# EMF_Trinket.net
KiCad netlist of a schematic drawn in EAGLE
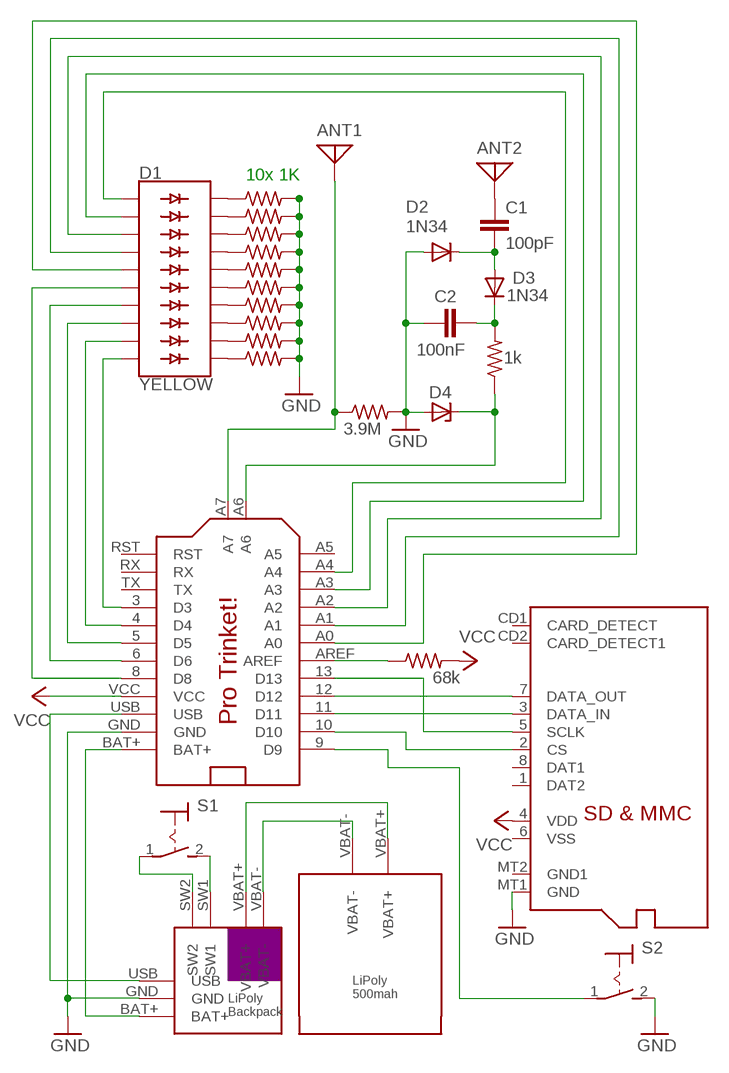
[diagram p0: schematic, sheet 1]

(export (version "E")
  (design (tool "Eeschema 10.0.6"))
  (components
    (comp (ref "ANT1")
      (value "ANTENNA")
      (footprint "eagle-import:PAD-01")
      (libsource (lib "eagle-import") (part "ANTENNA"))
    )
    (comp (ref "ANT2")
      (value "ANTENNA")
      (footprint "eagle-import:PAD-01")
      (libsource (lib "eagle-import") (part "ANTENNA"))
    )
    (comp (ref "C1")
      (value "100pF")
      (footprint "eagle-import:C5B2.5")
      (libsource (lib "eagle-import") (part "C5/2.5"))
    )
    (comp (ref "C2")
      (value "100nF")
      (footprint "eagle-import:C5B2.5")
      (libsource (lib "eagle-import") (part "C5/2.5"))
    )
    (comp (ref "D1")
      (value "YELLOW")
      (footprint "eagle-import:LED_BARGRAPH_10")
      (libsource (lib "eagle-import") (part "LED_BARGRAPH_10YELLOW"))
    )
    (comp (ref "D2")
      (value "1N34")
      (footprint "eagle-import:DO07")
      (libsource (lib "eagle-import") (part "AA112"))
    )
    (comp (ref "D3")
      (value "1N34")
      (footprint "eagle-import:DO07")
      (libsource (lib "eagle-import") (part "AA112"))
    )
    (comp (ref "D4")
      (value "ZENER-DIODEDO35Z10")
      (footprint "eagle-import:DO35Z10")
      (libsource (lib "eagle-import") (part "ZENER-DIODEDO35Z10"))
    )
    (comp (ref "R1")
      (value "R-US_0204/2V")
      (footprint "eagle-import:0204V")
      (libsource (lib "eagle-import") (part "R-US_0204/2V"))
    )
    (comp (ref "R2")
      (value "R-US_0204/2V")
      (footprint "eagle-import:0204V")
      (libsource (lib "eagle-import") (part "R-US_0204/2V"))
    )
    (comp (ref "R3")
      (value "R-US_0204/2V")
      (footprint "eagle-import:0204V")
      (libsource (lib "eagle-import") (part "R-US_0204/2V"))
    )
    (comp (ref "R4")
      (value "R-US_0204/2V")
      (footprint "eagle-import:0204V")
      (libsource (lib "eagle-import") (part "R-US_0204/2V"))
    )
    (comp (ref "R5")
      (value "R-US_0204/2V")
      (footprint "eagle-import:0204V")
      (libsource (lib "eagle-import") (part "R-US_0204/2V"))
    )
    (comp (ref "R6")
      (value "R-US_0204/2V")
      (footprint "eagle-import:0204V")
      (libsource (lib "eagle-import") (part "R-US_0204/2V"))
    )
    (comp (ref "R7")
      (value "R-US_0204/2V")
      (footprint "eagle-import:0204V")
      (libsource (lib "eagle-import") (part "R-US_0204/2V"))
    )
    (comp (ref "R8")
      (value "R-US_0204/2V")
      (footprint "eagle-import:0204V")
      (libsource (lib "eagle-import") (part "R-US_0204/2V"))
    )
    (comp (ref "R9")
      (value "R-US_0204/2V")
      (footprint "eagle-import:0204V")
      (libsource (lib "eagle-import") (part "R-US_0204/2V"))
    )
    (comp (ref "R10")
      (value "R-US_0204/2V")
      (footprint "eagle-import:0204V")
      (libsource (lib "eagle-import") (part "R-US_0204/2V"))
    )
    (comp (ref "R11")
      (value "1k")
      (footprint "eagle-import:0204V")
      (libsource (lib "eagle-import") (part "R-US_0204/2V"))
    )
    (comp (ref "R12")
      (value "3.9M")
      (footprint "eagle-import:0204V")
      (libsource (lib "eagle-import") (part "R-US_0204/2V"))
    )
    (comp (ref "R13")
      (value "68k")
      (footprint "eagle-import:0204V")
      (libsource (lib "eagle-import") (part "R-US_0204/2V"))
    )
    (comp (ref "S1")
      (value "MS243")
      (footprint "eagle-import:MS243")
      (libsource (lib "eagle-import") (part "MS243"))
    )
    (comp (ref "S2")
      (value "MS243")
      (footprint "eagle-import:MS243")
      (libsource (lib "eagle-import") (part "MS243"))
    )
    (comp (ref "U$1")
      (value "PRO_TRINKET")
      (footprint "eagle-import:PROTRINKET")
      (libsource (lib "eagle-import") (part "PRO_TRINKET"))
    )
    (comp (ref "U$2")
      (value "LIPOLY_BACKPACK")
      (footprint "eagle-import:LIPOLY_BACKPACK")
      (libsource (lib "eagle-import") (part "LIPOLY_BACKPACK"))
    )
    (comp (ref "U$3")
      (value "MICROSD")
      (footprint "eagle-import:MICROSD")
      (libsource (lib "eagle-import") (part "MICROSD"))
    )
    (comp (ref "U$4")
      (value "LIPOLY_BATTERY")
      (footprint "eagle-import:LIPOLY_BATTERY")
      (libsource (lib "eagle-import") (part "LIPOLY_BATTERY"))
    )
  )
  (nets
    (net (code "1") (name "/GND1") (class "Default")
      (node (ref "U$3") (pin "MT2") (pinfunction "GND1_MT2") (pintype "power_in"))
    )
    (net (code "2") (name "/VSS") (class "Default")
      (node (ref "U$3") (pin "6") (pinfunction "VSS_6") (pintype "power_in"))
    )
    (net (code "3") (name "GND") (class "Default")
      (node (ref "C2") (pin "1") (pinfunction "1_1") (pintype "passive"))
      (node (ref "D2") (pin "A") (pinfunction "A_A") (pintype "passive"))
      (node (ref "D4") (pin "A") (pinfunction "A_A") (pintype "passive"))
      (node (ref "R1") (pin "2") (pinfunction "2_2") (pintype "passive"))
      (node (ref "R10") (pin "2") (pinfunction "2_2") (pintype "passive"))
      (node (ref "R12") (pin "2") (pinfunction "2_2") (pintype "passive"))
      (node (ref "R2") (pin "2") (pinfunction "2_2") (pintype "passive"))
      (node (ref "R3") (pin "2") (pinfunction "2_2") (pintype "passive"))
      (node (ref "R4") (pin "2") (pinfunction "2_2") (pintype "passive"))
      (node (ref "R5") (pin "2") (pinfunction "2_2") (pintype "passive"))
      (node (ref "R6") (pin "2") (pinfunction "2_2") (pintype "passive"))
      (node (ref "R7") (pin "2") (pinfunction "2_2") (pintype "passive"))
      (node (ref "R8") (pin "2") (pinfunction "2_2") (pintype "passive"))
      (node (ref "R9") (pin "2") (pinfunction "2_2") (pintype "passive"))
      (node (ref "S2") (pin "2") (pinfunction "S_2") (pintype "passive"))
      (node (ref "U$1") (pin "GND") (pinfunction "GND_GND") (pintype "power_in"))
      (node (ref "U$2") (pin "GND") (pinfunction "GND_GND") (pintype "bidirectional"))
      (node (ref "U$3") (pin "MT1") (pinfunction "GND_MT1") (pintype "power_in"))
    )
    (net (code "4") (name "Net-(ANT1-Pad1)") (class "Default")
      (node (ref "ANT1") (pin "1") (pinfunction "1_1") (pintype "output"))
      (node (ref "R12") (pin "1") (pinfunction "1_1") (pintype "passive"))
      (node (ref "U$1") (pin "A7") (pinfunction "A7_A7") (pintype "passive"))
    )
    (net (code "5") (name "Net-(ANT2-Pad1)") (class "Default")
      (node (ref "ANT2") (pin "1") (pinfunction "1_1") (pintype "output"))
      (node (ref "C1") (pin "1") (pinfunction "1_1") (pintype "passive"))
    )
    (net (code "6") (name "Net-(C1-Pad2)") (class "Default")
      (node (ref "C1") (pin "2") (pinfunction "2_2") (pintype "passive"))
      (node (ref "D2") (pin "C") (pinfunction "C_C") (pintype "passive"))
      (node (ref "D3") (pin "A") (pinfunction "A_A") (pintype "passive"))
    )
    (net (code "7") (name "Net-(C2-Pad2)") (class "Default")
      (node (ref "C2") (pin "2") (pinfunction "2_2") (pintype "passive"))
      (node (ref "D3") (pin "C") (pinfunction "C_C") (pintype "passive"))
      (node (ref "R11") (pin "2") (pinfunction "2_2") (pintype "passive"))
    )
    (net (code "8") (name "Net-(D1-A)") (class "Default")
      (node (ref "D1") (pin "1") (pinfunction "A_1") (pintype "passive"))
      (node (ref "U$1") (pin "A4") (pinfunction "A4_A4") (pintype "bidirectional"))
    )
    (net (code "9") (name "Net-(D1-A1)") (class "Default")
      (node (ref "D1") (pin "2") (pinfunction "A1_2") (pintype "passive"))
      (node (ref "U$1") (pin "A3") (pinfunction "A3_A3") (pintype "bidirectional"))
    )
    (net (code "10") (name "Net-(D1-A2)") (class "Default")
      (node (ref "D1") (pin "3") (pinfunction "A2_3") (pintype "passive"))
      (node (ref "U$1") (pin "A2") (pinfunction "A2_A2") (pintype "bidirectional"))
    )
    (net (code "11") (name "Net-(D1-A3)") (class "Default")
      (node (ref "D1") (pin "4") (pinfunction "A3_4") (pintype "passive"))
      (node (ref "U$1") (pin "A1") (pinfunction "A1_A1") (pintype "bidirectional"))
    )
    (net (code "12") (name "Net-(D1-A4)") (class "Default")
      (node (ref "D1") (pin "5") (pinfunction "A4_5") (pintype "passive"))
      (node (ref "U$1") (pin "A0") (pinfunction "A0_A0") (pintype "bidirectional"))
    )
    (net (code "13") (name "Net-(D1-A5)") (class "Default")
      (node (ref "D1") (pin "6") (pinfunction "A5_6") (pintype "passive"))
      (node (ref "U$1") (pin "8") (pinfunction "D8_8") (pintype "bidirectional"))
    )
    (net (code "14") (name "Net-(D1-A6)") (class "Default")
      (node (ref "D1") (pin "7") (pinfunction "A6_7") (pintype "passive"))
      (node (ref "U$1") (pin "6") (pinfunction "D6_6") (pintype "bidirectional"))
    )
    (net (code "15") (name "Net-(D1-A7)") (class "Default")
      (node (ref "D1") (pin "8") (pinfunction "A7_8") (pintype "passive"))
      (node (ref "U$1") (pin "5") (pinfunction "D5_5") (pintype "bidirectional"))
    )
    (net (code "16") (name "Net-(D1-A8)") (class "Default")
      (node (ref "D1") (pin "9") (pinfunction "A8_9") (pintype "passive"))
      (node (ref "U$1") (pin "4") (pinfunction "D4_4") (pintype "bidirectional"))
    )
    (net (code "17") (name "Net-(D1-A9)") (class "Default")
      (node (ref "D1") (pin "10") (pinfunction "A9_10") (pintype "passive"))
      (node (ref "U$1") (pin "3") (pinfunction "D3_3") (pintype "bidirectional"))
    )
    (net (code "18") (name "Net-(D1-C)") (class "Default")
      (node (ref "D1") (pin "20") (pinfunction "C_20") (pintype "passive"))
      (node (ref "R1") (pin "1") (pinfunction "1_1") (pintype "passive"))
    )
    (net (code "19") (name "Net-(D1-C1)") (class "Default")
      (node (ref "D1") (pin "19") (pinfunction "C1_19") (pintype "passive"))
      (node (ref "R2") (pin "1") (pinfunction "1_1") (pintype "passive"))
    )
    (net (code "20") (name "Net-(D1-C2)") (class "Default")
      (node (ref "D1") (pin "18") (pinfunction "C2_18") (pintype "passive"))
      (node (ref "R3") (pin "1") (pinfunction "1_1") (pintype "passive"))
    )
    (net (code "21") (name "Net-(D1-C3)") (class "Default")
      (node (ref "D1") (pin "17") (pinfunction "C3_17") (pintype "passive"))
      (node (ref "R4") (pin "1") (pinfunction "1_1") (pintype "passive"))
    )
    (net (code "22") (name "Net-(D1-C4)") (class "Default")
      (node (ref "D1") (pin "16") (pinfunction "C4_16") (pintype "passive"))
      (node (ref "R5") (pin "1") (pinfunction "1_1") (pintype "passive"))
    )
    (net (code "23") (name "Net-(D1-C5)") (class "Default")
      (node (ref "D1") (pin "15") (pinfunction "C5_15") (pintype "passive"))
      (node (ref "R6") (pin "1") (pinfunction "1_1") (pintype "passive"))
    )
    (net (code "24") (name "Net-(D1-C6)") (class "Default")
      (node (ref "D1") (pin "14") (pinfunction "C6_14") (pintype "passive"))
      (node (ref "R7") (pin "1") (pinfunction "1_1") (pintype "passive"))
    )
    (net (code "25") (name "Net-(D1-C7)") (class "Default")
      (node (ref "D1") (pin "13") (pinfunction "C7_13") (pintype "passive"))
      (node (ref "R8") (pin "1") (pinfunction "1_1") (pintype "passive"))
    )
    (net (code "26") (name "Net-(D1-C8)") (class "Default")
      (node (ref "D1") (pin "12") (pinfunction "C8_12") (pintype "passive"))
      (node (ref "R9") (pin "1") (pinfunction "1_1") (pintype "passive"))
    )
    (net (code "27") (name "Net-(D1-C9)") (class "Default")
      (node (ref "D1") (pin "11") (pinfunction "C9_11") (pintype "passive"))
      (node (ref "R10") (pin "1") (pinfunction "1_1") (pintype "passive"))
    )
    (net (code "28") (name "Net-(D4-PadC)") (class "Default")
      (node (ref "D4") (pin "C") (pinfunction "C_C") (pintype "passive"))
      (node (ref "R11") (pin "1") (pinfunction "1_1") (pintype "passive"))
      (node (ref "U$1") (pin "A6") (pinfunction "A6_A6") (pintype "passive"))
    )
    (net (code "29") (name "Net-(R13-Pad1)") (class "Default")
      (node (ref "R13") (pin "1") (pinfunction "1_1") (pintype "passive"))
      (node (ref "U$1") (pin "AREF") (pinfunction "AREF_AREF") (pintype "passive"))
    )
    (net (code "30") (name "Net-(S1-P)") (class "Default")
      (node (ref "S1") (pin "1") (pinfunction "P_1") (pintype "passive"))
      (node (ref "U$2") (pin "SW2") (pinfunction "SW2_SW2") (pintype "bidirectional"))
    )
    (net (code "31") (name "Net-(S1-S)") (class "Default")
      (node (ref "S1") (pin "2") (pinfunction "S_2") (pintype "passive"))
      (node (ref "U$2") (pin "SW1") (pinfunction "SW1_SW1") (pintype "bidirectional"))
    )
    (net (code "32") (name "Net-(S2-P)") (class "Default")
      (node (ref "S2") (pin "1") (pinfunction "P_1") (pintype "passive"))
      (node (ref "U$1") (pin "9") (pinfunction "D9_9") (pintype "bidirectional"))
    )
    (net (code "33") (name "Net-(U$1-D10)") (class "Default")
      (node (ref "U$1") (pin "10") (pinfunction "D10_10") (pintype "bidirectional"))
      (node (ref "U$3") (pin "2") (pinfunction "CS_2") (pintype "input"))
    )
    (net (code "34") (name "Net-(U$1-D11)") (class "Default")
      (node (ref "U$1") (pin "11") (pinfunction "D11_11") (pintype "bidirectional"))
      (node (ref "U$3") (pin "3") (pinfunction "DATA_IN_3") (pintype "input"))
    )
    (net (code "35") (name "Net-(U$1-D12)") (class "Default")
      (node (ref "U$1") (pin "12") (pinfunction "D12_12") (pintype "bidirectional"))
      (node (ref "U$3") (pin "7") (pinfunction "DATA_OUT_7") (pintype "output"))
    )
    (net (code "36") (name "Net-(U$1-D13)") (class "Default")
      (node (ref "U$1") (pin "13") (pinfunction "D13_13") (pintype "bidirectional"))
      (node (ref "U$3") (pin "5") (pinfunction "SCLK_5") (pintype "input"))
    )
    (net (code "37") (name "Net-(U$1-PadBAT+)") (class "Default")
      (node (ref "U$1") (pin "BAT+") (pinfunction "BAT+_BAT+") (pintype "power_in"))
      (node (ref "U$2") (pin "BAT+") (pinfunction "BAT+_BAT+") (pintype "bidirectional"))
    )
    (net (code "38") (name "Net-(U$1-PadUSB)") (class "Default")
      (node (ref "U$1") (pin "USB") (pinfunction "USB_USB") (pintype "power_in"))
      (node (ref "U$2") (pin "USB") (pinfunction "USB_USB") (pintype "bidirectional"))
    )
    (net (code "39") (name "Net-(U$2-PadVBAT+)") (class "Default")
      (node (ref "U$2") (pin "VBAT+") (pinfunction "VBAT+_VBAT+") (pintype "bidirectional"))
      (node (ref "U$4") (pin "VBAT+") (pinfunction "VBAT+_VBAT+") (pintype "bidirectional"))
    )
    (net (code "40") (name "Net-(U$2-PadVBAT-)") (class "Default")
      (node (ref "U$2") (pin "VBAT-") (pinfunction "VBAT-_VBAT-") (pintype "bidirectional"))
      (node (ref "U$4") (pin "VBAT-") (pinfunction "VBAT-_VBAT-") (pintype "bidirectional"))
    )
    (net (code "41") (name "VCC") (class "Default")
      (node (ref "R13") (pin "2") (pinfunction "2_2") (pintype "passive"))
      (node (ref "U$1") (pin "VCC") (pinfunction "VCC_VCC") (pintype "power_in"))
      (node (ref "U$3") (pin "4") (pinfunction "VDD_4") (pintype "power_in"))
    )
    (net (code "42") (name "unconnected-(U$1-PadA5)") (class "Default")
      (node (ref "U$1") (pin "A5") (pinfunction "A5_A5") (pintype "bidirectional"))
    )
    (net (code "43") (name "unconnected-(U$1-PadRST)") (class "Default")
      (node (ref "U$1") (pin "RST") (pinfunction "RST_RST") (pintype "passive"))
    )
    (net (code "44") (name "unconnected-(U$1-PadRX)") (class "Default")
      (node (ref "U$1") (pin "RX") (pinfunction "RX_RX") (pintype "bidirectional"))
    )
    (net (code "45") (name "unconnected-(U$1-PadTX)") (class "Default")
      (node (ref "U$1") (pin "TX") (pinfunction "TX_TX") (pintype "bidirectional"))
    )
    (net (code "46") (name "unconnected-(U$3-CARD_DETECT-PadCD1)") (class "Default")
      (node (ref "U$3") (pin "CD1") (pinfunction "CARD_DETECT_CD1") (pintype "passive"))
    )
    (net (code "47") (name "unconnected-(U$3-CARD_DETECT1-PadCD2)") (class "Default")
      (node (ref "U$3") (pin "CD2") (pinfunction "CARD_DETECT1_CD2") (pintype "passive"))
    )
    (net (code "48") (name "unconnected-(U$3-DAT1-Pad8)") (class "Default")
      (node (ref "U$3") (pin "8") (pinfunction "DAT1_8") (pintype "bidirectional"))
    )
    (net (code "49") (name "unconnected-(U$3-DAT2-Pad1)") (class "Default")
      (node (ref "U$3") (pin "1") (pinfunction "DAT2_1") (pintype "bidirectional"))
    )
  )
)
